# mod_io.net
KiCad netlist of a schematic drawn in EAGLE
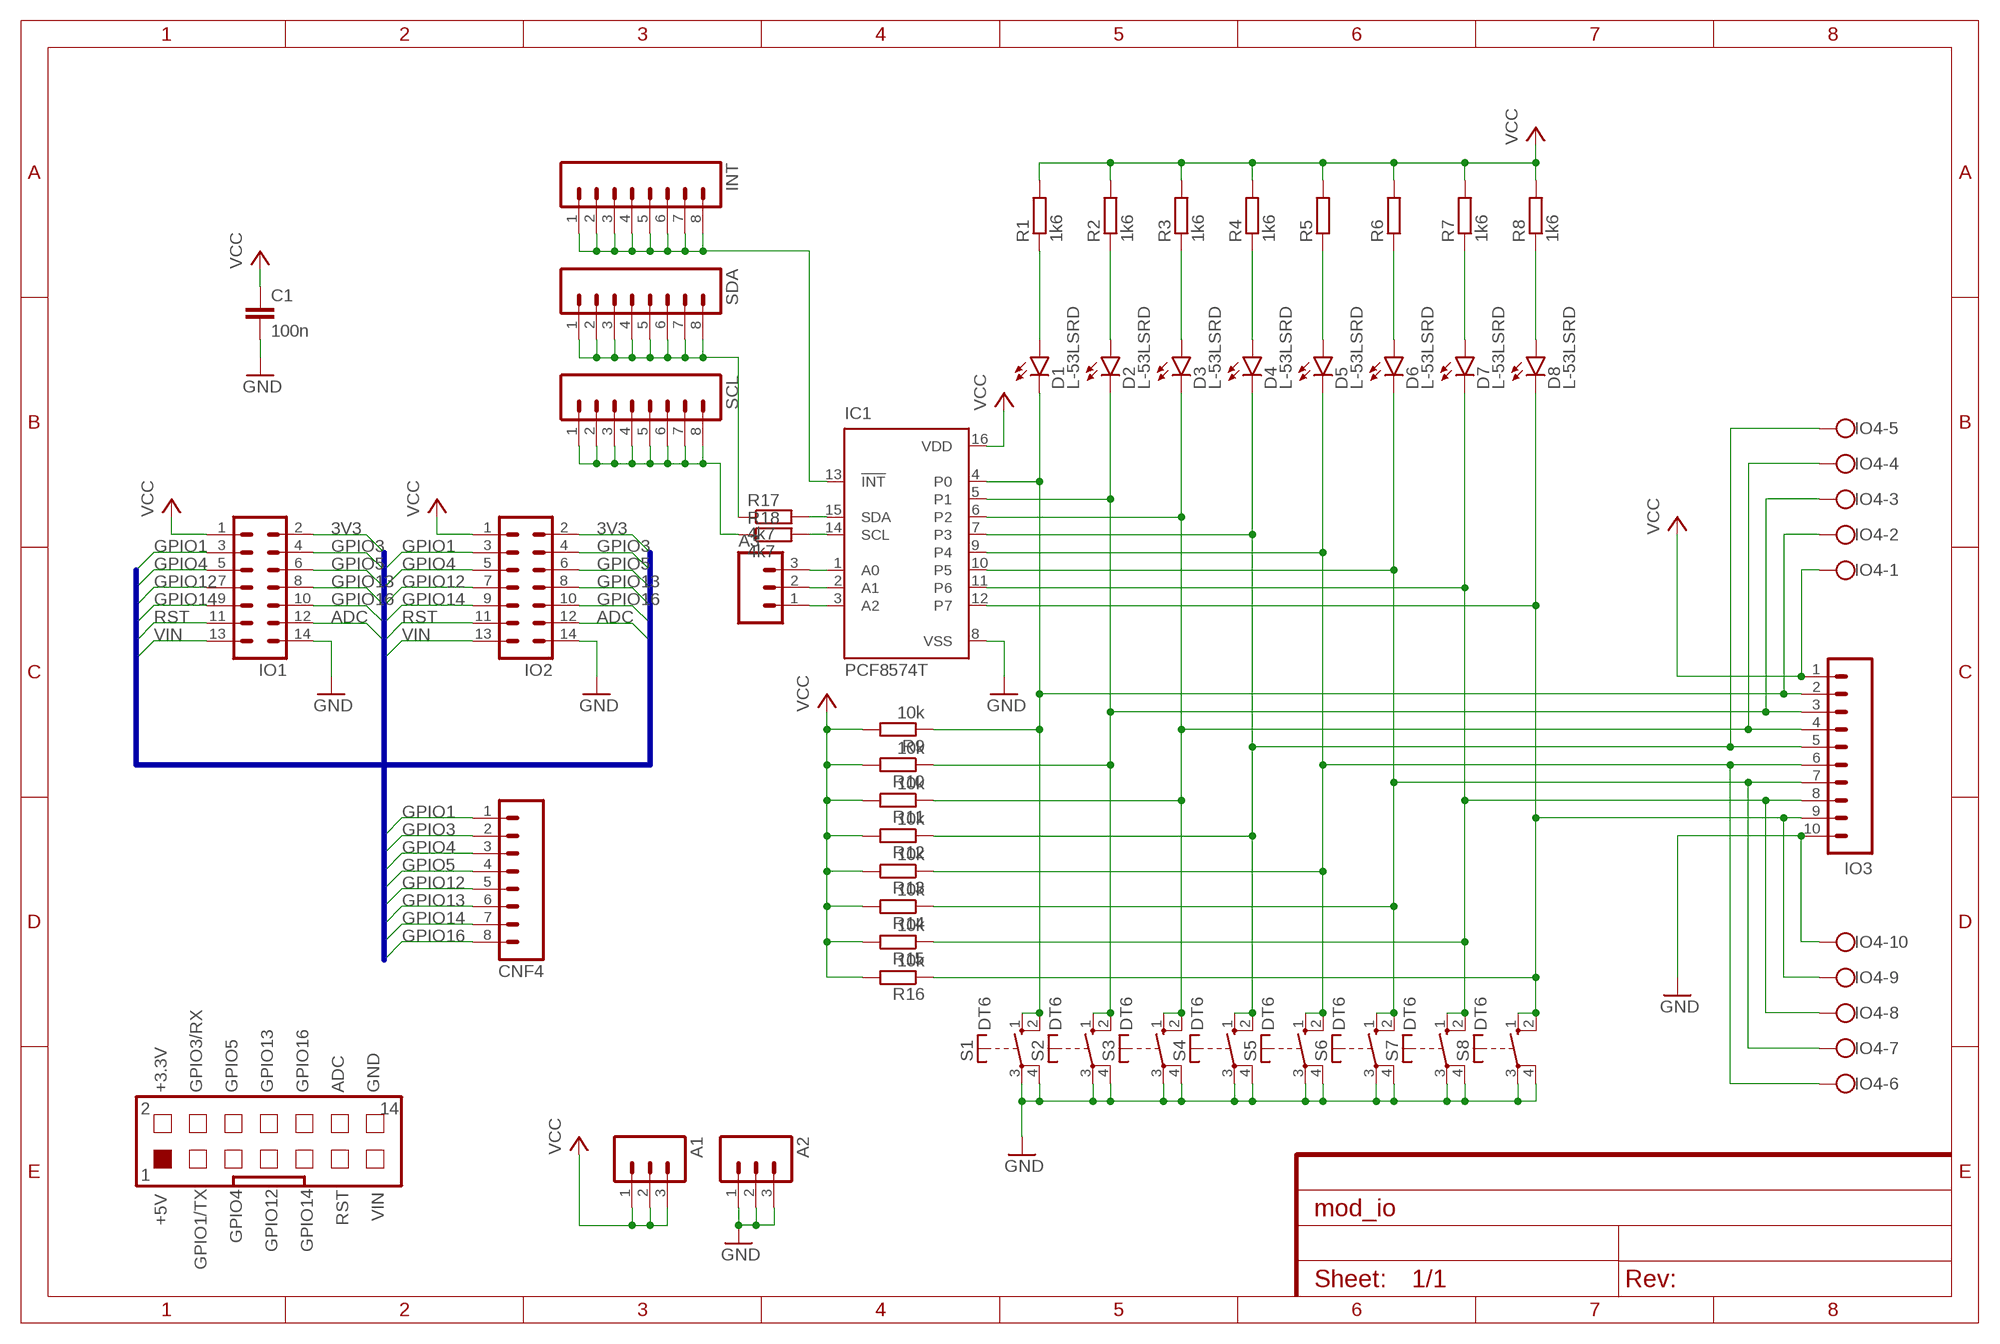
[diagram p0: schematic, sheet 1]

(export (version "E")
  (design (tool "Eeschema 10.0.6"))
  (components
    (comp (ref "A1")
      (value "M03LONGPADS")
      (footprint "eagle-import:1X03_LONGPADS")
      (libsource (lib "eagle-import") (part "M03LONGPADS"))
    )
    (comp (ref "A2")
      (value "M03LONGPADS")
      (footprint "eagle-import:1X03_LONGPADS")
      (libsource (lib "eagle-import") (part "M03LONGPADS"))
    )
    (comp (ref "A3")
      (value "M03LONGPADS")
      (footprint "eagle-import:1X03_LONGPADS")
      (libsource (lib "eagle-import") (part "M03LONGPADS"))
    )
    (comp (ref "C1")
      (value "100n")
      (footprint "eagle-import:C050-025X075")
      (libsource (lib "eagle-import") (part "C-EU050-025X075"))
    )
    (comp (ref "CNF4")
      (value "M08LONGPADS")
      (footprint "eagle-import:1X08_LONGPADS")
      (libsource (lib "eagle-import") (part "M08LONGPADS"))
    )
    (comp (ref "D1")
      (value "L-53LSRD")
      (footprint "eagle-import:LED5MM")
      (libsource (lib "eagle-import") (part "LED5MM"))
    )
    (comp (ref "D2")
      (value "L-53LSRD")
      (footprint "eagle-import:LED5MM")
      (libsource (lib "eagle-import") (part "LED5MM"))
    )
    (comp (ref "D3")
      (value "L-53LSRD")
      (footprint "eagle-import:LED5MM")
      (libsource (lib "eagle-import") (part "LED5MM"))
    )
    (comp (ref "D4")
      (value "L-53LSRD")
      (footprint "eagle-import:LED5MM")
      (libsource (lib "eagle-import") (part "LED5MM"))
    )
    (comp (ref "D5")
      (value "L-53LSRD")
      (footprint "eagle-import:LED5MM")
      (libsource (lib "eagle-import") (part "LED5MM"))
    )
    (comp (ref "D6")
      (value "L-53LSRD")
      (footprint "eagle-import:LED5MM")
      (libsource (lib "eagle-import") (part "LED5MM"))
    )
    (comp (ref "D7")
      (value "L-53LSRD")
      (footprint "eagle-import:LED5MM")
      (libsource (lib "eagle-import") (part "LED5MM"))
    )
    (comp (ref "D8")
      (value "L-53LSRD")
      (footprint "eagle-import:LED5MM")
      (libsource (lib "eagle-import") (part "LED5MM"))
    )
    (comp (ref "IC1")
      (value "PCF8574T")
      (footprint "eagle-import:SO16W")
      (fields (field (name "MPN") "PCF8574T/3,512"))
      (libsource (lib "eagle-import") (part "PCF8574T"))
    )
    (comp (ref "INT")
      (value "M08LONGPADS")
      (footprint "eagle-import:1X08_LONGPADS")
      (libsource (lib "eagle-import") (part "M08LONGPADS"))
    )
    (comp (ref "IO1")
      (value "14V")
      (footprint "eagle-import:14V")
      (libsource (lib "eagle-import") (part "14V"))
    )
    (comp (ref "IO2")
      (value "14V")
      (footprint "eagle-import:14V")
      (libsource (lib "eagle-import") (part "14V"))
    )
    (comp (ref "IO3")
      (value "M10LOCK_LONGPADS")
      (footprint "eagle-import:1X10_LOCK_LONGPADS")
      (libsource (lib "eagle-import") (part "M10LOCK_LONGPADS"))
    )
    (comp (ref "IO4")
      (value "AK550/10")
      (footprint "eagle-import:AK550_10")
      (libsource (lib "eagle-import") (part "AK550/10"))
    )
    (comp (ref "R1")
      (value "1k6")
      (footprint "eagle-import:0207_10")
      (libsource (lib "eagle-import") (part "R-EU_0207/10"))
    )
    (comp (ref "R2")
      (value "1k6")
      (footprint "eagle-import:0207_10")
      (libsource (lib "eagle-import") (part "R-EU_0207/10"))
    )
    (comp (ref "R3")
      (value "1k6")
      (footprint "eagle-import:0207_10")
      (libsource (lib "eagle-import") (part "R-EU_0207/10"))
    )
    (comp (ref "R4")
      (value "1k6")
      (footprint "eagle-import:0207_10")
      (libsource (lib "eagle-import") (part "R-EU_0207/10"))
    )
    (comp (ref "R5")
      (value "R-EU_0207/10")
      (footprint "eagle-import:0207_10")
      (libsource (lib "eagle-import") (part "R-EU_0207/10"))
    )
    (comp (ref "R6")
      (value "R-EU_0207/10")
      (footprint "eagle-import:0207_10")
      (libsource (lib "eagle-import") (part "R-EU_0207/10"))
    )
    (comp (ref "R7")
      (value "1k6")
      (footprint "eagle-import:0207_10")
      (libsource (lib "eagle-import") (part "R-EU_0207/10"))
    )
    (comp (ref "R8")
      (value "1k6")
      (footprint "eagle-import:0207_10")
      (libsource (lib "eagle-import") (part "R-EU_0207/10"))
    )
    (comp (ref "R9")
      (value "10k")
      (footprint "eagle-import:0207_10")
      (libsource (lib "eagle-import") (part "R-EU_0207/10"))
    )
    (comp (ref "R10")
      (value "10k")
      (footprint "eagle-import:0207_10")
      (libsource (lib "eagle-import") (part "R-EU_0207/10"))
    )
    (comp (ref "R11")
      (value "10k")
      (footprint "eagle-import:0207_10")
      (libsource (lib "eagle-import") (part "R-EU_0207/10"))
    )
    (comp (ref "R12")
      (value "10k")
      (footprint "eagle-import:0207_10")
      (libsource (lib "eagle-import") (part "R-EU_0207/10"))
    )
    (comp (ref "R13")
      (value "10k")
      (footprint "eagle-import:0207_10")
      (libsource (lib "eagle-import") (part "R-EU_0207/10"))
    )
    (comp (ref "R14")
      (value "10k")
      (footprint "eagle-import:0207_10")
      (libsource (lib "eagle-import") (part "R-EU_0207/10"))
    )
    (comp (ref "R15")
      (value "10k")
      (footprint "eagle-import:0207_10")
      (libsource (lib "eagle-import") (part "R-EU_0207/10"))
    )
    (comp (ref "R16")
      (value "10k")
      (footprint "eagle-import:0207_10")
      (libsource (lib "eagle-import") (part "R-EU_0207/10"))
    )
    (comp (ref "R17")
      (value "4k7")
      (footprint "eagle-import:0207_10")
      (libsource (lib "eagle-import") (part "R-EU_0207/10"))
    )
    (comp (ref "R18")
      (value "4k7")
      (footprint "eagle-import:0207_10")
      (libsource (lib "eagle-import") (part "R-EU_0207/10"))
    )
    (comp (ref "S1")
      (value "DT6")
      (footprint "eagle-import:DT6")
      (libsource (lib "eagle-import") (part "DT6"))
    )
    (comp (ref "S2")
      (value "DT6")
      (footprint "eagle-import:DT6")
      (libsource (lib "eagle-import") (part "DT6"))
    )
    (comp (ref "S3")
      (value "DT6")
      (footprint "eagle-import:DT6")
      (libsource (lib "eagle-import") (part "DT6"))
    )
    (comp (ref "S4")
      (value "DT6")
      (footprint "eagle-import:DT6")
      (libsource (lib "eagle-import") (part "DT6"))
    )
    (comp (ref "S5")
      (value "DT6")
      (footprint "eagle-import:DT6")
      (libsource (lib "eagle-import") (part "DT6"))
    )
    (comp (ref "S6")
      (value "DT6")
      (footprint "eagle-import:DT6")
      (libsource (lib "eagle-import") (part "DT6"))
    )
    (comp (ref "S7")
      (value "DT6")
      (footprint "eagle-import:DT6")
      (libsource (lib "eagle-import") (part "DT6"))
    )
    (comp (ref "S8")
      (value "DT6")
      (footprint "eagle-import:DT6")
      (libsource (lib "eagle-import") (part "DT6"))
    )
    (comp (ref "SCL")
      (value "M08LONGPADS")
      (footprint "eagle-import:1X08_LONGPADS")
      (libsource (lib "eagle-import") (part "M08LONGPADS"))
    )
    (comp (ref "SDA")
      (value "M08LONGPADS")
      (footprint "eagle-import:1X08_LONGPADS")
      (libsource (lib "eagle-import") (part "M08LONGPADS"))
    )
  )
  (nets
    (net (code "1") (name "/3V3") (class "Default")
      (node (ref "IO1") (pin "2") (pinfunction "2_2") (pintype "passive"))
      (node (ref "IO2") (pin "2") (pinfunction "2_2") (pintype "passive"))
    )
    (net (code "2") (name "/ADC") (class "Default")
      (node (ref "IO1") (pin "12") (pinfunction "12_12") (pintype "passive"))
      (node (ref "IO2") (pin "12") (pinfunction "12_12") (pintype "passive"))
    )
    (net (code "3") (name "/GPIO1") (class "Default")
      (node (ref "CNF4") (pin "1") (pinfunction "1_1") (pintype "passive"))
      (node (ref "IO1") (pin "3") (pinfunction "3_3") (pintype "passive"))
      (node (ref "IO2") (pin "3") (pinfunction "3_3") (pintype "passive"))
    )
    (net (code "4") (name "/GPIO3") (class "Default")
      (node (ref "CNF4") (pin "2") (pinfunction "2_2") (pintype "passive"))
      (node (ref "IO1") (pin "4") (pinfunction "4_4") (pintype "passive"))
      (node (ref "IO2") (pin "4") (pinfunction "4_4") (pintype "passive"))
    )
    (net (code "5") (name "/GPIO4") (class "Default")
      (node (ref "CNF4") (pin "3") (pinfunction "3_3") (pintype "passive"))
      (node (ref "IO1") (pin "5") (pinfunction "5_5") (pintype "passive"))
      (node (ref "IO2") (pin "5") (pinfunction "5_5") (pintype "passive"))
    )
    (net (code "6") (name "/GPIO5") (class "Default")
      (node (ref "CNF4") (pin "4") (pinfunction "4_4") (pintype "passive"))
      (node (ref "IO1") (pin "6") (pinfunction "6_6") (pintype "passive"))
      (node (ref "IO2") (pin "6") (pinfunction "6_6") (pintype "passive"))
    )
    (net (code "7") (name "/GPIO12") (class "Default")
      (node (ref "CNF4") (pin "5") (pinfunction "5_5") (pintype "passive"))
      (node (ref "IO1") (pin "7") (pinfunction "7_7") (pintype "passive"))
      (node (ref "IO2") (pin "7") (pinfunction "7_7") (pintype "passive"))
    )
    (net (code "8") (name "/GPIO13") (class "Default")
      (node (ref "CNF4") (pin "6") (pinfunction "6_6") (pintype "passive"))
      (node (ref "IO1") (pin "8") (pinfunction "8_8") (pintype "passive"))
      (node (ref "IO2") (pin "8") (pinfunction "8_8") (pintype "passive"))
    )
    (net (code "9") (name "/GPIO14") (class "Default")
      (node (ref "CNF4") (pin "7") (pinfunction "7_7") (pintype "passive"))
      (node (ref "IO1") (pin "9") (pinfunction "9_9") (pintype "passive"))
      (node (ref "IO2") (pin "9") (pinfunction "9_9") (pintype "passive"))
    )
    (net (code "10") (name "/GPIO16") (class "Default")
      (node (ref "CNF4") (pin "8") (pinfunction "8_8") (pintype "passive"))
      (node (ref "IO1") (pin "10") (pinfunction "10_10") (pintype "passive"))
      (node (ref "IO2") (pin "10") (pinfunction "10_10") (pintype "passive"))
    )
    (net (code "11") (name "/RST") (class "Default")
      (node (ref "IO1") (pin "11") (pinfunction "11_11") (pintype "passive"))
      (node (ref "IO2") (pin "11") (pinfunction "11_11") (pintype "passive"))
    )
    (net (code "12") (name "/VIN") (class "Default")
      (node (ref "IO1") (pin "13") (pinfunction "13_13") (pintype "passive"))
      (node (ref "IO2") (pin "13") (pinfunction "13_13") (pintype "passive"))
    )
    (net (code "13") (name "GND") (class "Default")
      (node (ref "A2") (pin "1") (pinfunction "1_1") (pintype "passive"))
      (node (ref "A2") (pin "2") (pinfunction "2_2") (pintype "passive"))
      (node (ref "A2") (pin "3") (pinfunction "3_3") (pintype "passive"))
      (node (ref "C1") (pin "2") (pinfunction "2_2") (pintype "passive"))
      (node (ref "IC1") (pin "8") (pinfunction "VSS_8") (pintype "power_in"))
      (node (ref "IO1") (pin "14") (pinfunction "14_14") (pintype "passive"))
      (node (ref "IO2") (pin "14") (pinfunction "14_14") (pintype "passive"))
      (node (ref "IO3") (pin "10") (pinfunction "10_10") (pintype "passive"))
      (node (ref "IO4") (pin "10") (pinfunction "KL_10") (pintype "passive"))
      (node (ref "S1") (pin "3") (pinfunction "P_3") (pintype "passive"))
      (node (ref "S1") (pin "4") (pinfunction "P_4") (pintype "passive"))
      (node (ref "S2") (pin "3") (pinfunction "P_3") (pintype "passive"))
      (node (ref "S2") (pin "4") (pinfunction "P_4") (pintype "passive"))
      (node (ref "S3") (pin "3") (pinfunction "P_3") (pintype "passive"))
      (node (ref "S3") (pin "4") (pinfunction "P_4") (pintype "passive"))
      (node (ref "S4") (pin "3") (pinfunction "P_3") (pintype "passive"))
      (node (ref "S4") (pin "4") (pinfunction "P_4") (pintype "passive"))
      (node (ref "S5") (pin "3") (pinfunction "P_3") (pintype "passive"))
      (node (ref "S5") (pin "4") (pinfunction "P_4") (pintype "passive"))
      (node (ref "S6") (pin "3") (pinfunction "P_3") (pintype "passive"))
      (node (ref "S6") (pin "4") (pinfunction "P_4") (pintype "passive"))
      (node (ref "S7") (pin "3") (pinfunction "P_3") (pintype "passive"))
      (node (ref "S7") (pin "4") (pinfunction "P_4") (pintype "passive"))
      (node (ref "S8") (pin "3") (pinfunction "P_3") (pintype "passive"))
      (node (ref "S8") (pin "4") (pinfunction "P_4") (pintype "passive"))
    )
    (net (code "14") (name "Net-(D1-C)") (class "Default")
      (node (ref "D1") (pin "K") (pinfunction "C_K") (pintype "passive"))
      (node (ref "IC1") (pin "4") (pinfunction "P0_4") (pintype "bidirectional"))
      (node (ref "IO3") (pin "2") (pinfunction "2_2") (pintype "passive"))
      (node (ref "IO4") (pin "2") (pinfunction "KL_2") (pintype "passive"))
      (node (ref "R9") (pin "1") (pinfunction "1_1") (pintype "passive"))
      (node (ref "S1") (pin "1") (pinfunction "S_1") (pintype "passive"))
      (node (ref "S1") (pin "2") (pinfunction "S_2") (pintype "passive"))
    )
    (net (code "15") (name "Net-(D1-PadA)") (class "Default")
      (node (ref "D1") (pin "A") (pinfunction "A_A") (pintype "passive"))
      (node (ref "R1") (pin "1") (pinfunction "1_1") (pintype "passive"))
    )
    (net (code "16") (name "Net-(D2-C)") (class "Default")
      (node (ref "D2") (pin "K") (pinfunction "C_K") (pintype "passive"))
      (node (ref "IC1") (pin "5") (pinfunction "P1_5") (pintype "bidirectional"))
      (node (ref "IO3") (pin "3") (pinfunction "3_3") (pintype "passive"))
      (node (ref "IO4") (pin "3") (pinfunction "KL_3") (pintype "passive"))
      (node (ref "R10") (pin "1") (pinfunction "1_1") (pintype "passive"))
      (node (ref "S2") (pin "1") (pinfunction "S_1") (pintype "passive"))
      (node (ref "S2") (pin "2") (pinfunction "S_2") (pintype "passive"))
    )
    (net (code "17") (name "Net-(D2-PadA)") (class "Default")
      (node (ref "D2") (pin "A") (pinfunction "A_A") (pintype "passive"))
      (node (ref "R2") (pin "1") (pinfunction "1_1") (pintype "passive"))
    )
    (net (code "18") (name "Net-(D3-C)") (class "Default")
      (node (ref "D3") (pin "K") (pinfunction "C_K") (pintype "passive"))
      (node (ref "IC1") (pin "6") (pinfunction "P2_6") (pintype "bidirectional"))
      (node (ref "IO3") (pin "4") (pinfunction "4_4") (pintype "passive"))
      (node (ref "IO4") (pin "4") (pinfunction "KL_4") (pintype "passive"))
      (node (ref "R11") (pin "1") (pinfunction "1_1") (pintype "passive"))
      (node (ref "S3") (pin "1") (pinfunction "S_1") (pintype "passive"))
      (node (ref "S3") (pin "2") (pinfunction "S_2") (pintype "passive"))
    )
    (net (code "19") (name "Net-(D3-PadA)") (class "Default")
      (node (ref "D3") (pin "A") (pinfunction "A_A") (pintype "passive"))
      (node (ref "R3") (pin "1") (pinfunction "1_1") (pintype "passive"))
    )
    (net (code "20") (name "Net-(D4-C)") (class "Default")
      (node (ref "D4") (pin "K") (pinfunction "C_K") (pintype "passive"))
      (node (ref "IC1") (pin "7") (pinfunction "P3_7") (pintype "bidirectional"))
      (node (ref "IO3") (pin "5") (pinfunction "5_5") (pintype "passive"))
      (node (ref "IO4") (pin "5") (pinfunction "KL_5") (pintype "passive"))
      (node (ref "R12") (pin "1") (pinfunction "1_1") (pintype "passive"))
      (node (ref "S4") (pin "1") (pinfunction "S_1") (pintype "passive"))
      (node (ref "S4") (pin "2") (pinfunction "S_2") (pintype "passive"))
    )
    (net (code "21") (name "Net-(D4-PadA)") (class "Default")
      (node (ref "D4") (pin "A") (pinfunction "A_A") (pintype "passive"))
      (node (ref "R4") (pin "1") (pinfunction "1_1") (pintype "passive"))
    )
    (net (code "22") (name "Net-(D5-C)") (class "Default")
      (node (ref "D5") (pin "K") (pinfunction "C_K") (pintype "passive"))
      (node (ref "IC1") (pin "9") (pinfunction "P4_9") (pintype "bidirectional"))
      (node (ref "IO3") (pin "6") (pinfunction "6_6") (pintype "passive"))
      (node (ref "IO4") (pin "6") (pinfunction "KL_6") (pintype "passive"))
      (node (ref "R13") (pin "1") (pinfunction "1_1") (pintype "passive"))
      (node (ref "S5") (pin "1") (pinfunction "S_1") (pintype "passive"))
      (node (ref "S5") (pin "2") (pinfunction "S_2") (pintype "passive"))
    )
    (net (code "23") (name "Net-(D5-PadA)") (class "Default")
      (node (ref "D5") (pin "A") (pinfunction "A_A") (pintype "passive"))
      (node (ref "R5") (pin "1") (pinfunction "1_1") (pintype "passive"))
    )
    (net (code "24") (name "Net-(D6-C)") (class "Default")
      (node (ref "D6") (pin "K") (pinfunction "C_K") (pintype "passive"))
      (node (ref "IC1") (pin "10") (pinfunction "P5_10") (pintype "bidirectional"))
      (node (ref "IO3") (pin "7") (pinfunction "7_7") (pintype "passive"))
      (node (ref "IO4") (pin "7") (pinfunction "KL_7") (pintype "passive"))
      (node (ref "R14") (pin "1") (pinfunction "1_1") (pintype "passive"))
      (node (ref "S6") (pin "1") (pinfunction "S_1") (pintype "passive"))
      (node (ref "S6") (pin "2") (pinfunction "S_2") (pintype "passive"))
    )
    (net (code "25") (name "Net-(D6-PadA)") (class "Default")
      (node (ref "D6") (pin "A") (pinfunction "A_A") (pintype "passive"))
      (node (ref "R6") (pin "1") (pinfunction "1_1") (pintype "passive"))
    )
    (net (code "26") (name "Net-(D7-C)") (class "Default")
      (node (ref "D7") (pin "K") (pinfunction "C_K") (pintype "passive"))
      (node (ref "IC1") (pin "11") (pinfunction "P6_11") (pintype "bidirectional"))
      (node (ref "IO3") (pin "8") (pinfunction "8_8") (pintype "passive"))
      (node (ref "IO4") (pin "8") (pinfunction "KL_8") (pintype "passive"))
      (node (ref "R15") (pin "1") (pinfunction "1_1") (pintype "passive"))
      (node (ref "S7") (pin "1") (pinfunction "S_1") (pintype "passive"))
      (node (ref "S7") (pin "2") (pinfunction "S_2") (pintype "passive"))
    )
    (net (code "27") (name "Net-(D7-PadA)") (class "Default")
      (node (ref "D7") (pin "A") (pinfunction "A_A") (pintype "passive"))
      (node (ref "R7") (pin "1") (pinfunction "1_1") (pintype "passive"))
    )
    (net (code "28") (name "Net-(D8-C)") (class "Default")
      (node (ref "D8") (pin "K") (pinfunction "C_K") (pintype "passive"))
      (node (ref "IC1") (pin "12") (pinfunction "P7_12") (pintype "bidirectional"))
      (node (ref "IO3") (pin "9") (pinfunction "9_9") (pintype "passive"))
      (node (ref "IO4") (pin "9") (pinfunction "KL_9") (pintype "passive"))
      (node (ref "R16") (pin "1") (pinfunction "1_1") (pintype "passive"))
      (node (ref "S8") (pin "1") (pinfunction "S_1") (pintype "passive"))
      (node (ref "S8") (pin "2") (pinfunction "S_2") (pintype "passive"))
    )
    (net (code "29") (name "Net-(D8-PadA)") (class "Default")
      (node (ref "D8") (pin "A") (pinfunction "A_A") (pintype "passive"))
      (node (ref "R8") (pin "1") (pinfunction "1_1") (pintype "passive"))
    )
    (net (code "30") (name "Net-(IC1-A0)") (class "Default")
      (node (ref "A3") (pin "3") (pinfunction "3_3") (pintype "passive"))
      (node (ref "IC1") (pin "1") (pinfunction "A0_1") (pintype "input"))
    )
    (net (code "31") (name "Net-(IC1-A1)") (class "Default")
      (node (ref "A3") (pin "2") (pinfunction "2_2") (pintype "passive"))
      (node (ref "IC1") (pin "2") (pinfunction "A1_2") (pintype "input"))
    )
    (net (code "32") (name "Net-(IC1-A2)") (class "Default")
      (node (ref "A3") (pin "1") (pinfunction "1_1") (pintype "passive"))
      (node (ref "IC1") (pin "3") (pinfunction "A2_3") (pintype "input"))
    )
    (net (code "33") (name "Net-(IC1-SCL)") (class "Default")
      (node (ref "IC1") (pin "14") (pinfunction "SCL_14") (pintype "input"))
      (node (ref "R18") (pin "2") (pinfunction "2_2") (pintype "passive"))
    )
    (net (code "34") (name "Net-(IC1-SDA)") (class "Default")
      (node (ref "IC1") (pin "15") (pinfunction "SDA_15") (pintype "bidirectional"))
      (node (ref "R17") (pin "2") (pinfunction "2_2") (pintype "passive"))
    )
    (net (code "35") (name "Net-(IC1-~{INT})") (class "Default")
      (node (ref "IC1") (pin "13") (pinfunction "~{INT}_13") (pintype "output"))
      (node (ref "INT") (pin "1") (pinfunction "1_1") (pintype "passive"))
      (node (ref "INT") (pin "2") (pinfunction "2_2") (pintype "passive"))
      (node (ref "INT") (pin "3") (pinfunction "3_3") (pintype "passive"))
      (node (ref "INT") (pin "4") (pinfunction "4_4") (pintype "passive"))
      (node (ref "INT") (pin "5") (pinfunction "5_5") (pintype "passive"))
      (node (ref "INT") (pin "6") (pinfunction "6_6") (pintype "passive"))
      (node (ref "INT") (pin "7") (pinfunction "7_7") (pintype "passive"))
      (node (ref "INT") (pin "8") (pinfunction "8_8") (pintype "passive"))
    )
    (net (code "36") (name "Net-(R17-Pad1)") (class "Default")
      (node (ref "R17") (pin "1") (pinfunction "1_1") (pintype "passive"))
      (node (ref "SDA") (pin "1") (pinfunction "1_1") (pintype "passive"))
      (node (ref "SDA") (pin "2") (pinfunction "2_2") (pintype "passive"))
      (node (ref "SDA") (pin "3") (pinfunction "3_3") (pintype "passive"))
      (node (ref "SDA") (pin "4") (pinfunction "4_4") (pintype "passive"))
      (node (ref "SDA") (pin "5") (pinfunction "5_5") (pintype "passive"))
      (node (ref "SDA") (pin "6") (pinfunction "6_6") (pintype "passive"))
      (node (ref "SDA") (pin "7") (pinfunction "7_7") (pintype "passive"))
      (node (ref "SDA") (pin "8") (pinfunction "8_8") (pintype "passive"))
    )
    (net (code "37") (name "Net-(R18-Pad1)") (class "Default")
      (node (ref "R18") (pin "1") (pinfunction "1_1") (pintype "passive"))
      (node (ref "SCL") (pin "1") (pinfunction "1_1") (pintype "passive"))
      (node (ref "SCL") (pin "2") (pinfunction "2_2") (pintype "passive"))
      (node (ref "SCL") (pin "3") (pinfunction "3_3") (pintype "passive"))
      (node (ref "SCL") (pin "4") (pinfunction "4_4") (pintype "passive"))
      (node (ref "SCL") (pin "5") (pinfunction "5_5") (pintype "passive"))
      (node (ref "SCL") (pin "6") (pinfunction "6_6") (pintype "passive"))
      (node (ref "SCL") (pin "7") (pinfunction "7_7") (pintype "passive"))
      (node (ref "SCL") (pin "8") (pinfunction "8_8") (pintype "passive"))
    )
    (net (code "38") (name "VCC") (class "Default")
      (node (ref "A1") (pin "1") (pinfunction "1_1") (pintype "passive"))
      (node (ref "A1") (pin "2") (pinfunction "2_2") (pintype "passive"))
      (node (ref "A1") (pin "3") (pinfunction "3_3") (pintype "passive"))
      (node (ref "C1") (pin "1") (pinfunction "1_1") (pintype "passive"))
      (node (ref "IC1") (pin "16") (pinfunction "VDD_16") (pintype "power_in"))
      (node (ref "IO1") (pin "1") (pinfunction "1_1") (pintype "passive"))
      (node (ref "IO2") (pin "1") (pinfunction "1_1") (pintype "passive"))
      (node (ref "IO3") (pin "1") (pinfunction "1_1") (pintype "passive"))
      (node (ref "IO4") (pin "1") (pinfunction "KL_1") (pintype "passive"))
      (node (ref "R1") (pin "2") (pinfunction "2_2") (pintype "passive"))
      (node (ref "R10") (pin "2") (pinfunction "2_2") (pintype "passive"))
      (node (ref "R11") (pin "2") (pinfunction "2_2") (pintype "passive"))
      (node (ref "R12") (pin "2") (pinfunction "2_2") (pintype "passive"))
      (node (ref "R13") (pin "2") (pinfunction "2_2") (pintype "passive"))
      (node (ref "R14") (pin "2") (pinfunction "2_2") (pintype "passive"))
      (node (ref "R15") (pin "2") (pinfunction "2_2") (pintype "passive"))
      (node (ref "R16") (pin "2") (pinfunction "2_2") (pintype "passive"))
      (node (ref "R2") (pin "2") (pinfunction "2_2") (pintype "passive"))
      (node (ref "R3") (pin "2") (pinfunction "2_2") (pintype "passive"))
      (node (ref "R4") (pin "2") (pinfunction "2_2") (pintype "passive"))
      (node (ref "R5") (pin "2") (pinfunction "2_2") (pintype "passive"))
      (node (ref "R6") (pin "2") (pinfunction "2_2") (pintype "passive"))
      (node (ref "R7") (pin "2") (pinfunction "2_2") (pintype "passive"))
      (node (ref "R8") (pin "2") (pinfunction "2_2") (pintype "passive"))
      (node (ref "R9") (pin "2") (pinfunction "2_2") (pintype "passive"))
    )
  )
)
